# TV-B-Gone.net
KiCad netlist of a schematic drawn in EAGLE
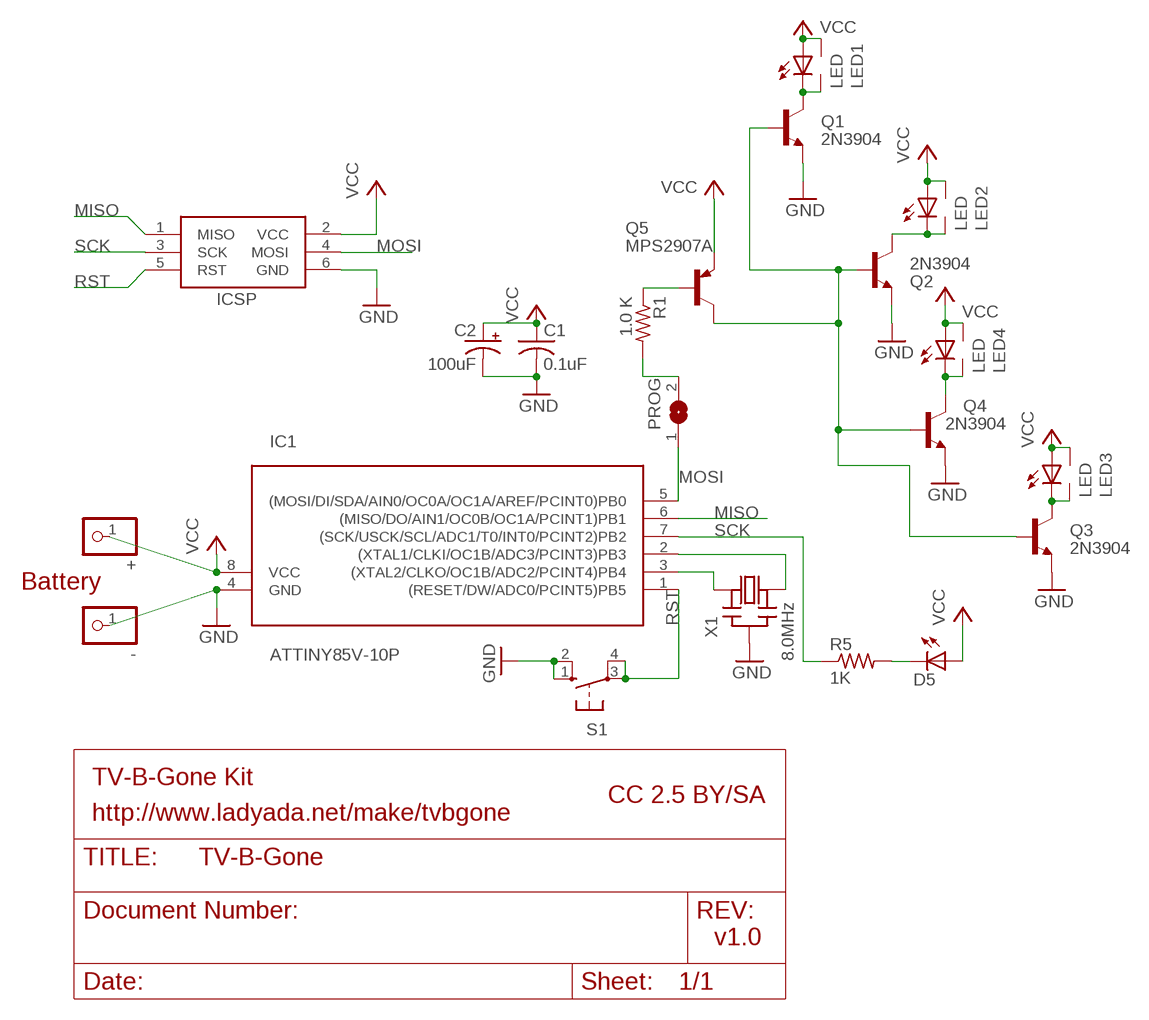
[diagram p0: schematic, sheet 1]

(export (version "E")
  (design (tool "Eeschema 10.0.6"))
  (components
    (comp (ref "+")
      (value "PINHD-1X1CB")
      (footprint "eagle-import:1X01-CLEANBIG")
      (libsource (lib "eagle-import") (part "PINHD-1X1CB"))
    )
    (comp (ref "-")
      (value "PINHD-1X1CB")
      (footprint "eagle-import:1X01-CLEANBIG")
      (libsource (lib "eagle-import") (part "PINHD-1X1CB"))
    )
    (comp (ref "C1")
      (value "0.1uF")
      (footprint "eagle-import:C025-025X050")
      (libsource (lib "eagle-import") (part "C-US025-025X050"))
    )
    (comp (ref "C2")
      (value "100uF")
      (footprint "eagle-import:E-2.54-0511-HOR")
      (libsource (lib "eagle-import") (part "CAP-POL_E-2.54-0511-HOR"))
    )
    (comp (ref "D5")
      (value "LED3MM")
      (footprint "eagle-import:LED3MM")
      (libsource (lib "eagle-import") (part "LED3MM"))
    )
    (comp (ref "IC1")
      (value "ATTINY85V-10P")
      (footprint "eagle-import:DIL08")
      (libsource (lib "eagle-import") (part "ATTINY85PV-10"))
    )
    (comp (ref "ICSP")
      (value "AVRISP-6")
      (footprint "eagle-import:AVRISP")
      (libsource (lib "eagle-import") (part "AVRISP-6"))
    )
    (comp (ref "LED1")
      (value "LED")
      (footprint "eagle-import:5MM-SIDE")
      (libsource (lib "eagle-import") (part "tvbgone_LED"))
    )
    (comp (ref "LED2")
      (value "LED")
      (footprint "eagle-import:5MM-SIDE")
      (libsource (lib "eagle-import") (part "tvbgone_LED"))
    )
    (comp (ref "LED3")
      (value "LED")
      (footprint "eagle-import:5MM-SIDE")
      (libsource (lib "eagle-import") (part "tvbgone_LED"))
    )
    (comp (ref "LED4")
      (value "LED")
      (footprint "eagle-import:5MM-SIDE")
      (libsource (lib "eagle-import") (part "tvbgone_LED"))
    )
    (comp (ref "PROG")
      (value "SJ")
      (footprint "eagle-import:SJ")
      (libsource (lib "eagle-import") (part "SJ"))
    )
    (comp (ref "Q1")
      (value "2N3904")
      (footprint "eagle-import:TO92-EBC")
      (libsource (lib "eagle-import") (part "-NPN-TO92-EBC2N3904"))
    )
    (comp (ref "Q2")
      (value "2N3904")
      (footprint "eagle-import:TO92-EBC")
      (libsource (lib "eagle-import") (part "-NPN-TO92-EBC2N3904"))
    )
    (comp (ref "Q3")
      (value "2N3904")
      (footprint "eagle-import:TO92-EBC")
      (libsource (lib "eagle-import") (part "-NPN-TO92-EBC2N3904"))
    )
    (comp (ref "Q4")
      (value "2N3904")
      (footprint "eagle-import:TO92-EBC")
      (libsource (lib "eagle-import") (part "-NPN-TO92-EBC2N3904"))
    )
    (comp (ref "Q5")
      (value "MPS2907A")
      (footprint "eagle-import:TO92-CBE")
      (libsource (lib "eagle-import") (part "MPS2907A"))
    )
    (comp (ref "R1")
      (value "1.0 K")
      (footprint "eagle-import:0207_10")
      (libsource (lib "eagle-import") (part "R-US_0207/10"))
    )
    (comp (ref "R5")
      (value "1K")
      (footprint "eagle-import:0207_10")
      (libsource (lib "eagle-import") (part "R-US_0207/10"))
    )
    (comp (ref "S1")
      (value "10-XX")
      (footprint "eagle-import:B3F-10XX")
      (fields (field (name "MPN") "B3F-1000"))
      (libsource (lib "eagle-import") (part "10-XX"))
    )
    (comp (ref "X1")
      (value "8.0MHz")
      (footprint "eagle-import:CERM_OSC")
      (libsource (lib "eagle-import") (part "CERMOSCILL-THM"))
    )
  )
  (nets
    (net (code "1") (name "/MISO") (class "Default")
      (node (ref "IC1") (pin "6") (pinfunction "(MISO/DO/AIN1/OC0B/OC1A/PCINT1)PB1_6") (pintype "bidirectional"))
      (node (ref "ICSP") (pin "1") (pinfunction "MISO_1") (pintype "input"))
    )
    (net (code "2") (name "/MOSI") (class "Default")
      (node (ref "IC1") (pin "5") (pinfunction "(MOSI/DI/SDA/AIN0/OC0A/OC1A/AREF/PCINT0)PB0_5") (pintype "bidirectional"))
      (node (ref "ICSP") (pin "4") (pinfunction "MOSI_4") (pintype "output"))
      (node (ref "PROG") (pin "1") (pinfunction "1_1") (pintype "passive"))
    )
    (net (code "3") (name "/RST") (class "Default")
      (node (ref "IC1") (pin "1") (pinfunction "(RESET/DW/ADC0/PCINT5)PB5_1") (pintype "bidirectional"))
      (node (ref "ICSP") (pin "5") (pinfunction "RST_5") (pintype "output"))
      (node (ref "S1") (pin "3") (pinfunction "P_3") (pintype "passive"))
      (node (ref "S1") (pin "4") (pinfunction "P1_4") (pintype "passive"))
    )
    (net (code "4") (name "/SCK") (class "Default")
      (node (ref "IC1") (pin "7") (pinfunction "(SCK/USCK/SCL/ADC1/T0/INT0/PCINT2)PB2_7") (pintype "bidirectional"))
      (node (ref "ICSP") (pin "3") (pinfunction "SCK_3") (pintype "output"))
      (node (ref "R5") (pin "1") (pinfunction "1_1") (pintype "passive"))
    )
    (net (code "5") (name "GND") (class "Default")
      (node (ref "-") (pin "1") (pinfunction "1_1") (pintype "passive"))
      (node (ref "C1") (pin "2") (pinfunction "2_2") (pintype "passive"))
      (node (ref "C2") (pin "-") (pinfunction "-_-") (pintype "passive"))
      (node (ref "IC1") (pin "4") (pinfunction "GND_4") (pintype "bidirectional"))
      (node (ref "ICSP") (pin "6") (pinfunction "GND_6") (pintype "power_in"))
      (node (ref "Q1") (pin "E") (pinfunction "E_E") (pintype "passive"))
      (node (ref "Q2") (pin "E") (pinfunction "E_E") (pintype "passive"))
      (node (ref "Q3") (pin "E") (pinfunction "E_E") (pintype "passive"))
      (node (ref "Q4") (pin "E") (pinfunction "E_E") (pintype "passive"))
      (node (ref "S1") (pin "1") (pinfunction "S_1") (pintype "passive"))
      (node (ref "S1") (pin "2") (pinfunction "S1_2") (pintype "passive"))
      (node (ref "X1") (pin "P$2") (pinfunction "GND_P$2") (pintype "bidirectional"))
    )
    (net (code "6") (name "Net-(D5-C)") (class "Default")
      (node (ref "D5") (pin "K") (pinfunction "C_K") (pintype "passive"))
      (node (ref "R5") (pin "2") (pinfunction "2_2") (pintype "passive"))
    )
    (net (code "7") (name "Net-(IC1-(XTAL1{slash}CLKI{slash}OC1B{slash}ADC3{slash}PCINT3)PB3)") (class "Default")
      (node (ref "IC1") (pin "2") (pinfunction "(XTAL1/CLKI/OC1B/ADC3/PCINT3)PB3_2") (pintype "bidirectional"))
      (node (ref "X1") (pin "P$3") (pinfunction "OUT_P$3") (pintype "bidirectional"))
    )
    (net (code "8") (name "Net-(IC1-(XTAL2{slash}CLKO{slash}OC1B{slash}ADC2{slash}PCINT4)PB4)") (class "Default")
      (node (ref "IC1") (pin "3") (pinfunction "(XTAL2/CLKO/OC1B/ADC2/PCINT4)PB4_3") (pintype "bidirectional"))
      (node (ref "X1") (pin "P$1") (pinfunction "IN_P$1") (pintype "bidirectional"))
    )
    (net (code "9") (name "Net-(LED1-C)") (class "Default")
      (node (ref "LED1") (pin "K") (pinfunction "C_K") (pintype "passive"))
      (node (ref "LED1") (pin "K2") (pinfunction "C1_K2") (pintype "passive"))
      (node (ref "Q1") (pin "C") (pinfunction "C_C") (pintype "passive"))
    )
    (net (code "10") (name "Net-(LED2-C)") (class "Default")
      (node (ref "LED2") (pin "K") (pinfunction "C_K") (pintype "passive"))
      (node (ref "LED2") (pin "K2") (pinfunction "C1_K2") (pintype "passive"))
      (node (ref "Q2") (pin "C") (pinfunction "C_C") (pintype "passive"))
    )
    (net (code "11") (name "Net-(LED3-C)") (class "Default")
      (node (ref "LED3") (pin "K") (pinfunction "C_K") (pintype "passive"))
      (node (ref "LED3") (pin "K2") (pinfunction "C1_K2") (pintype "passive"))
      (node (ref "Q3") (pin "C") (pinfunction "C_C") (pintype "passive"))
    )
    (net (code "12") (name "Net-(LED4-C)") (class "Default")
      (node (ref "LED4") (pin "K") (pinfunction "C_K") (pintype "passive"))
      (node (ref "LED4") (pin "K2") (pinfunction "C1_K2") (pintype "passive"))
      (node (ref "Q4") (pin "C") (pinfunction "C_C") (pintype "passive"))
    )
    (net (code "13") (name "Net-(PROG-Pad2)") (class "Default")
      (node (ref "PROG") (pin "2") (pinfunction "2_2") (pintype "passive"))
      (node (ref "R1") (pin "2") (pinfunction "2_2") (pintype "passive"))
    )
    (net (code "14") (name "Net-(Q1-PadB)") (class "Default")
      (node (ref "Q1") (pin "B") (pinfunction "B_B") (pintype "passive"))
      (node (ref "Q2") (pin "B") (pinfunction "B_B") (pintype "passive"))
      (node (ref "Q3") (pin "B") (pinfunction "B_B") (pintype "passive"))
      (node (ref "Q4") (pin "B") (pinfunction "B_B") (pintype "passive"))
      (node (ref "Q5") (pin "C") (pinfunction "C_C") (pintype "passive"))
    )
    (net (code "15") (name "Net-(Q5-PadB)") (class "Default")
      (node (ref "Q5") (pin "B") (pinfunction "B_B") (pintype "passive"))
      (node (ref "R1") (pin "1") (pinfunction "1_1") (pintype "passive"))
    )
    (net (code "16") (name "VCC") (class "Default")
      (node (ref "+") (pin "1") (pinfunction "1_1") (pintype "passive"))
      (node (ref "C1") (pin "1") (pinfunction "1_1") (pintype "passive"))
      (node (ref "C2") (pin "+") (pinfunction "+_+") (pintype "passive"))
      (node (ref "D5") (pin "A") (pinfunction "A_A") (pintype "passive"))
      (node (ref "IC1") (pin "8") (pinfunction "VCC_8") (pintype "bidirectional"))
      (node (ref "ICSP") (pin "2") (pinfunction "VCC_2") (pintype "power_in"))
      (node (ref "LED1") (pin "A") (pinfunction "A_A") (pintype "passive"))
      (node (ref "LED1") (pin "A2") (pinfunction "A1_A2") (pintype "passive"))
      (node (ref "LED2") (pin "A") (pinfunction "A_A") (pintype "passive"))
      (node (ref "LED2") (pin "A2") (pinfunction "A1_A2") (pintype "passive"))
      (node (ref "LED3") (pin "A") (pinfunction "A_A") (pintype "passive"))
      (node (ref "LED3") (pin "A2") (pinfunction "A1_A2") (pintype "passive"))
      (node (ref "LED4") (pin "A") (pinfunction "A_A") (pintype "passive"))
      (node (ref "LED4") (pin "A2") (pinfunction "A1_A2") (pintype "passive"))
      (node (ref "Q5") (pin "E") (pinfunction "E_E") (pintype "passive"))
    )
  )
)
